# jtag.net
KiCad netlist of a schematic drawn in Altium Designer
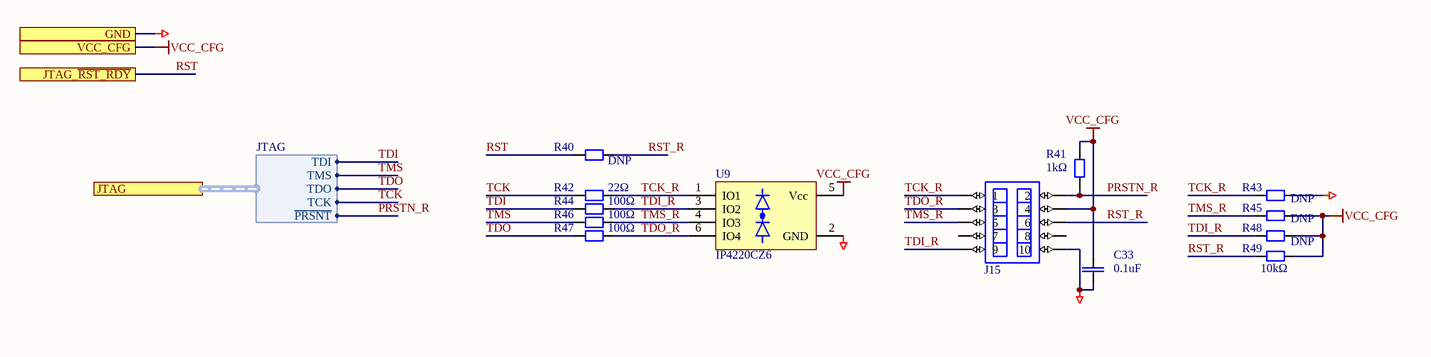
[diagram p0: jtag.SchDoc]

(export (version "E")
  (design (tool "Eeschema 10.0.6"))
  (components
    (comp (ref "C33")
      (value "0.1uF")
      (footprint "CAPC2012N")
      (description "Generic ceramic SMD capacitor")
      (fields (field (name "MAINTAINER") "Evgeniy Kotov"))
      (libsource (lib "[Capacitors] Capacitors SMD") (part "CAPC"))
    )
    (comp (ref "J15")
      (value "IDC-10MC")
      (footprint "PLD-10")
      (description "Connector, 5x2, Male, 2.54mm Pitch, Strait contacts, with Body")
      (fields (field (name "MAINTAINER") "Evgeniy Kotov"))
      (libsource (lib "[Connectors] Miscellaneous") (part "IDC-10MS"))
    )
    (comp (ref "R40")
      (value "DNP")
      (footprint "RESC1608N")
      (description "Resistor, Generic, SMD")
      (fields (field (name "MAINTAINER") "Evgeniy Kotov"))
      (libsource (lib "[Resistors] Resistors SMD") (part "RESC"))
    )
    (comp (ref "R41")
      (value "1kΩ")
      (footprint "RESC2012N")
      (description "Resistor, Generic, SMD")
      (fields (field (name "MAINTAINER") "Evgeniy Kotov"))
      (libsource (lib "[Resistors] Resistors SMD") (part "RESC"))
    )
    (comp (ref "R42")
      (value "22Ω")
      (footprint "RESC1608N")
      (description "Resistor, Generic, SMD")
      (fields (field (name "MAINTAINER") "Evgeniy Kotov"))
      (libsource (lib "[Resistors] Resistors SMD") (part "RESC"))
    )
    (comp (ref "R43")
      (value "DNP")
      (footprint "RESC2012N")
      (description "Resistor, Generic, SMD")
      (fields (field (name "MAINTAINER") "Evgeniy Kotov"))
      (libsource (lib "carrier") (part "RESC"))
    )
    (comp (ref "R44")
      (value "100Ω")
      (footprint "RESC1608N")
      (description "Resistor, Generic, SMD")
      (fields (field (name "MAINTAINER") "Evgeniy Kotov"))
      (libsource (lib "[Resistors] Resistors SMD") (part "RESC"))
    )
    (comp (ref "R45")
      (value "DNP")
      (footprint "RESC2012N")
      (description "Resistor, Generic, SMD")
      (fields (field (name "MAINTAINER") "Evgeniy Kotov"))
      (libsource (lib "carrier") (part "RESC"))
    )
    (comp (ref "R46")
      (value "100Ω")
      (footprint "RESC1608N")
      (description "Resistor, Generic, SMD")
      (fields (field (name "MAINTAINER") "Evgeniy Kotov"))
      (libsource (lib "[Resistors] Resistors SMD") (part "RESC"))
    )
    (comp (ref "R47")
      (value "100Ω")
      (footprint "RESC1608N")
      (description "Resistor, Generic, SMD")
      (fields (field (name "MAINTAINER") "Evgeniy Kotov"))
      (libsource (lib "[Resistors] Resistors SMD") (part "RESC"))
    )
    (comp (ref "R48")
      (value "DNP")
      (footprint "RESC2012N")
      (description "Resistor, Generic, SMD")
      (fields (field (name "MAINTAINER") "Evgeniy Kotov"))
      (libsource (lib "carrier") (part "RESC"))
    )
    (comp (ref "R49")
      (value "10kΩ")
      (footprint "RESC2012N")
      (description "Resistor, Generic, SMD")
      (fields (field (name "MAINTAINER") "Evgeniy Kotov"))
      (libsource (lib "carrier") (part "RESC"))
    )
    (comp (ref "U9")
      (value "IP4220CZ6")
      (footprint "SOT95P285X110-6N")
      (description "Transimpedance Amplifier; Selectable-Feedback Resistance")
      (fields (field (name "MAINTAINER") "Evgeniy Kotov"))
      (libsource (lib "[ICs And Semiconductors] Diodes") (part "IP4220CZ6"))
    )
  )
  (nets
    (net (code "2") (name "/PRSTN_R") (class "Default")
      (node (ref "J15") (pin "2") (pinfunction "2_2") (pintype "bidirectional"))
      (node (ref "R41") (pin "1") (pintype "passive"))
    )
    (net (code "3") (name "/RST") (class "Default") (node (ref "R40") (pin "1") (pintype "passive")))
    (net (code "4") (name "/RST_R") (class "Default")
      (node (ref "J15") (pin "6") (pinfunction "6_6") (pintype "bidirectional"))
      (node (ref "R40") (pin "2") (pintype "passive"))
      (node (ref "R49") (pin "1") (pintype "passive"))
    )
    (net (code "5") (name "/TCK") (class "Default") (node (ref "R42") (pin "1") (pintype "passive")))
    (net (code "6") (name "/TCK_R") (class "Default")
      (node (ref "J15") (pin "1") (pinfunction "1_1") (pintype "bidirectional"))
      (node (ref "R42") (pin "2") (pintype "passive"))
      (node (ref "R43") (pin "1") (pintype "passive"))
      (node (ref "U9") (pin "1") (pinfunction "IO1_1") (pintype "passive"))
    )
    (net (code "7") (name "/TDI") (class "Default") (node (ref "R44") (pin "1") (pintype "passive")))
    (net (code "8") (name "/TDI_R") (class "Default")
      (node (ref "J15") (pin "9") (pinfunction "9_9") (pintype "bidirectional"))
      (node (ref "R44") (pin "2") (pintype "passive"))
      (node (ref "R48") (pin "1") (pintype "passive"))
      (node (ref "U9") (pin "3") (pinfunction "IO2_3") (pintype "passive"))
    )
    (net (code "9") (name "/TDO") (class "Default") (node (ref "R47") (pin "1") (pintype "passive")))
    (net (code "10") (name "/TDO_R") (class "Default")
      (node (ref "J15") (pin "3") (pinfunction "3_3") (pintype "bidirectional"))
      (node (ref "R47") (pin "2") (pintype "passive"))
      (node (ref "U9") (pin "6") (pinfunction "IO4_6") (pintype "passive"))
    )
    (net (code "11") (name "/TMS") (class "Default") (node (ref "R46") (pin "1") (pintype "passive")))
    (net (code "12") (name "/TMS_R") (class "Default")
      (node (ref "J15") (pin "5") (pinfunction "5_5") (pintype "bidirectional"))
      (node (ref "R45") (pin "1") (pintype "passive"))
      (node (ref "R46") (pin "2") (pintype "passive"))
      (node (ref "U9") (pin "4") (pinfunction "IO3_4") (pintype "passive"))
    )
    (net (code "14") (name "GND") (class "Default")
      (node (ref "C33") (pin "1") (pintype "passive"))
      (node (ref "J15") (pin "10") (pinfunction "10_10") (pintype "bidirectional"))
      (node (ref "R43") (pin "2") (pintype "passive"))
      (node (ref "U9") (pin "2") (pinfunction "GND_2") (pintype "passive"))
    )
    (net (code "15") (name "VCC_CFG") (class "Default")
      (node (ref "C33") (pin "2") (pintype "passive"))
      (node (ref "J15") (pin "4") (pinfunction "4_4") (pintype "bidirectional"))
      (node (ref "R41") (pin "2") (pintype "passive"))
      (node (ref "R45") (pin "2") (pintype "passive"))
      (node (ref "R48") (pin "2") (pintype "passive"))
      (node (ref "R49") (pin "2") (pintype "passive"))
      (node (ref "U9") (pin "5") (pinfunction "Vcc_5") (pintype "passive"))
    )
    (net (code "16") (name "unconnected-(J15-Pad7)") (class "Default")
      (node (ref "J15") (pin "7") (pinfunction "7_7") (pintype "bidirectional"))
    )
    (net (code "17") (name "unconnected-(J15-Pad8)") (class "Default")
      (node (ref "J15") (pin "8") (pinfunction "8_8") (pintype "bidirectional"))
    )
  )
)
